# schematic.net
KiCad netlist of a schematic drawn in EAGLE
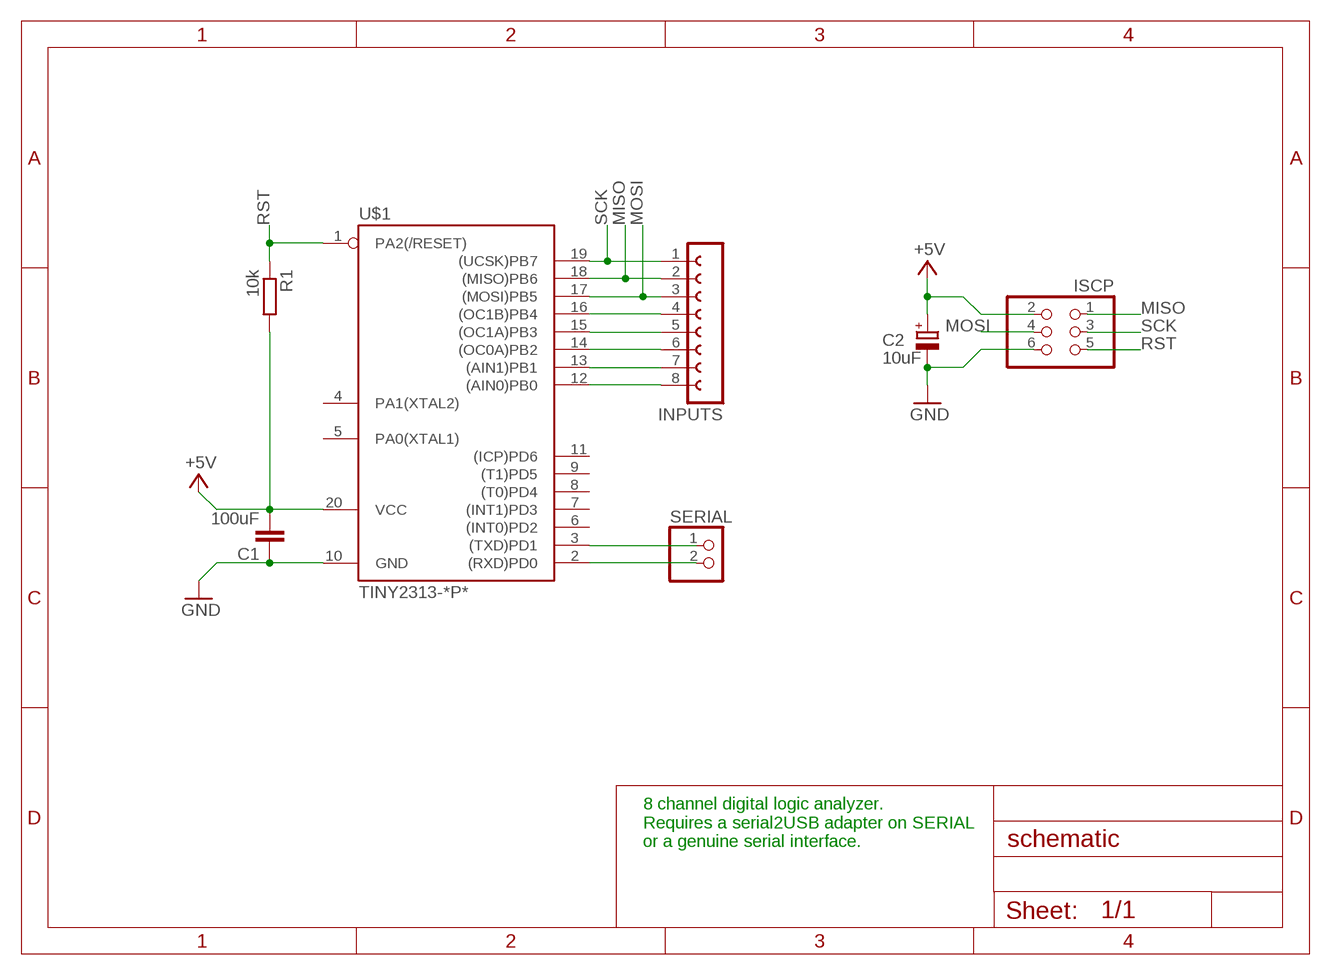
[diagram p0: schematic, sheet 1]

(export (version "E")
  (design (tool "Eeschema 10.0.6"))
  (components
    (comp (ref "C1")
      (value "100uF")
      (footprint "eagle-import:C025-024X044")
      (libsource (lib "eagle-import") (part "C-EU025-024X044"))
    )
    (comp (ref "C2")
      (value "10uF")
      (footprint "eagle-import:E2,5-6")
      (libsource (lib "eagle-import") (part "CPOL-EUE2.5-6"))
    )
    (comp (ref "INPUTS")
      (value "FE08W")
      (footprint "eagle-import:FE08W")
      (libsource (lib "eagle-import") (part "FE08W"))
    )
    (comp (ref "ISCP")
      (value "PINHD-2X3")
      (footprint "eagle-import:2X03")
      (libsource (lib "eagle-import") (part "PINHD-2X3"))
    )
    (comp (ref "R1")
      (value "10k")
      (footprint "eagle-import:0204V")
      (libsource (lib "eagle-import") (part "R-EU_0204/2V"))
    )
    (comp (ref "SERIAL")
      (value "PINHD-1X2")
      (footprint "eagle-import:1X02")
      (libsource (lib "eagle-import") (part "PINHD-1X2"))
    )
    (comp (ref "U$1")
      (value "TINY2313-*P*")
      (footprint "eagle-import:DIL20")
      (libsource (lib "eagle-import") (part "TINY2313-P"))
    )
  )
  (nets
    (net (code "1") (name "+5V") (class "Default")
      (node (ref "C1") (pin "2") (pinfunction "2_2") (pintype "passive"))
      (node (ref "C2") (pin "+") (pinfunction "+_+") (pintype "passive"))
      (node (ref "ISCP") (pin "2") (pinfunction "2_2") (pintype "passive"))
      (node (ref "R1") (pin "2") (pinfunction "2_2") (pintype "passive"))
      (node (ref "U$1") (pin "20") (pinfunction "VCC_20") (pintype "power_in"))
    )
    (net (code "2") (name "/MISO") (class "Default")
      (node (ref "INPUTS") (pin "2") (pinfunction "2_2") (pintype "passive"))
      (node (ref "ISCP") (pin "1") (pinfunction "1_1") (pintype "passive"))
      (node (ref "U$1") (pin "18") (pinfunction "(MISO)PB6_18") (pintype "bidirectional"))
    )
    (net (code "3") (name "/MOSI") (class "Default")
      (node (ref "INPUTS") (pin "3") (pinfunction "3_3") (pintype "passive"))
      (node (ref "ISCP") (pin "4") (pinfunction "4_4") (pintype "passive"))
      (node (ref "U$1") (pin "17") (pinfunction "(MOSI)PB5_17") (pintype "bidirectional"))
    )
    (net (code "4") (name "/RST") (class "Default")
      (node (ref "ISCP") (pin "5") (pinfunction "5_5") (pintype "passive"))
      (node (ref "R1") (pin "1") (pinfunction "1_1") (pintype "passive"))
      (node (ref "U$1") (pin "1") (pinfunction "PA2(/RESET)_1") (pintype "input"))
    )
    (net (code "5") (name "/SCK") (class "Default")
      (node (ref "INPUTS") (pin "1") (pinfunction "1_1") (pintype "passive"))
      (node (ref "ISCP") (pin "3") (pinfunction "3_3") (pintype "passive"))
      (node (ref "U$1") (pin "19") (pinfunction "(UCSK)PB7_19") (pintype "bidirectional"))
    )
    (net (code "6") (name "GND") (class "Default")
      (node (ref "C1") (pin "1") (pinfunction "1_1") (pintype "passive"))
      (node (ref "C2") (pin "-") (pinfunction "-_-") (pintype "passive"))
      (node (ref "ISCP") (pin "6") (pinfunction "6_6") (pintype "passive"))
      (node (ref "U$1") (pin "10") (pinfunction "GND_10") (pintype "power_in"))
    )
    (net (code "7") (name "Net-(U$1-(AIN0)PB0)") (class "Default")
      (node (ref "INPUTS") (pin "8") (pinfunction "8_8") (pintype "passive"))
      (node (ref "U$1") (pin "12") (pinfunction "(AIN0)PB0_12") (pintype "bidirectional"))
    )
    (net (code "8") (name "Net-(U$1-(AIN1)PB1)") (class "Default")
      (node (ref "INPUTS") (pin "7") (pinfunction "7_7") (pintype "passive"))
      (node (ref "U$1") (pin "13") (pinfunction "(AIN1)PB1_13") (pintype "bidirectional"))
    )
    (net (code "9") (name "Net-(U$1-(OC0A)PB2)") (class "Default")
      (node (ref "INPUTS") (pin "6") (pinfunction "6_6") (pintype "passive"))
      (node (ref "U$1") (pin "14") (pinfunction "(OC0A)PB2_14") (pintype "bidirectional"))
    )
    (net (code "10") (name "Net-(U$1-(OC1A)PB3)") (class "Default")
      (node (ref "INPUTS") (pin "5") (pinfunction "5_5") (pintype "passive"))
      (node (ref "U$1") (pin "15") (pinfunction "(OC1A)PB3_15") (pintype "bidirectional"))
    )
    (net (code "11") (name "Net-(U$1-(OC1B)PB4)") (class "Default")
      (node (ref "INPUTS") (pin "4") (pinfunction "4_4") (pintype "passive"))
      (node (ref "U$1") (pin "16") (pinfunction "(OC1B)PB4_16") (pintype "bidirectional"))
    )
    (net (code "12") (name "Net-(U$1-(RXD)PD0)") (class "Default")
      (node (ref "SERIAL") (pin "2") (pinfunction "2_2") (pintype "passive"))
      (node (ref "U$1") (pin "2") (pinfunction "(RXD)PD0_2") (pintype "bidirectional"))
    )
    (net (code "13") (name "Net-(U$1-(TXD)PD1)") (class "Default")
      (node (ref "SERIAL") (pin "1") (pinfunction "1_1") (pintype "passive"))
      (node (ref "U$1") (pin "3") (pinfunction "(TXD)PD1_3") (pintype "bidirectional"))
    )
    (net (code "14") (name "unconnected-(U$1-(ICP)PD6-Pad11)") (class "Default")
      (node (ref "U$1") (pin "11") (pinfunction "(ICP)PD6_11") (pintype "bidirectional"))
    )
    (net (code "15") (name "unconnected-(U$1-(INT0)PD2-Pad6)") (class "Default")
      (node (ref "U$1") (pin "6") (pinfunction "(INT0)PD2_6") (pintype "bidirectional"))
    )
    (net (code "16") (name "unconnected-(U$1-(INT1)PD3-Pad7)") (class "Default")
      (node (ref "U$1") (pin "7") (pinfunction "(INT1)PD3_7") (pintype "bidirectional"))
    )
    (net (code "17") (name "unconnected-(U$1-(T0)PD4-Pad8)") (class "Default")
      (node (ref "U$1") (pin "8") (pinfunction "(T0)PD4_8") (pintype "bidirectional"))
    )
    (net (code "18") (name "unconnected-(U$1-(T1)PD5-Pad9)") (class "Default")
      (node (ref "U$1") (pin "9") (pinfunction "(T1)PD5_9") (pintype "bidirectional"))
    )
    (net (code "19") (name "unconnected-(U$1-PA0(XTAL1)-Pad5)") (class "Default")
      (node (ref "U$1") (pin "5") (pinfunction "PA0(XTAL1)_5") (pintype "bidirectional"))
    )
    (net (code "20") (name "unconnected-(U$1-PA1(XTAL2)-Pad4)") (class "Default")
      (node (ref "U$1") (pin "4") (pinfunction "PA1(XTAL2)_4") (pintype "bidirectional"))
    )
  )
)
